# DotControl.net
KiCad netlist of a schematic drawn in EAGLE
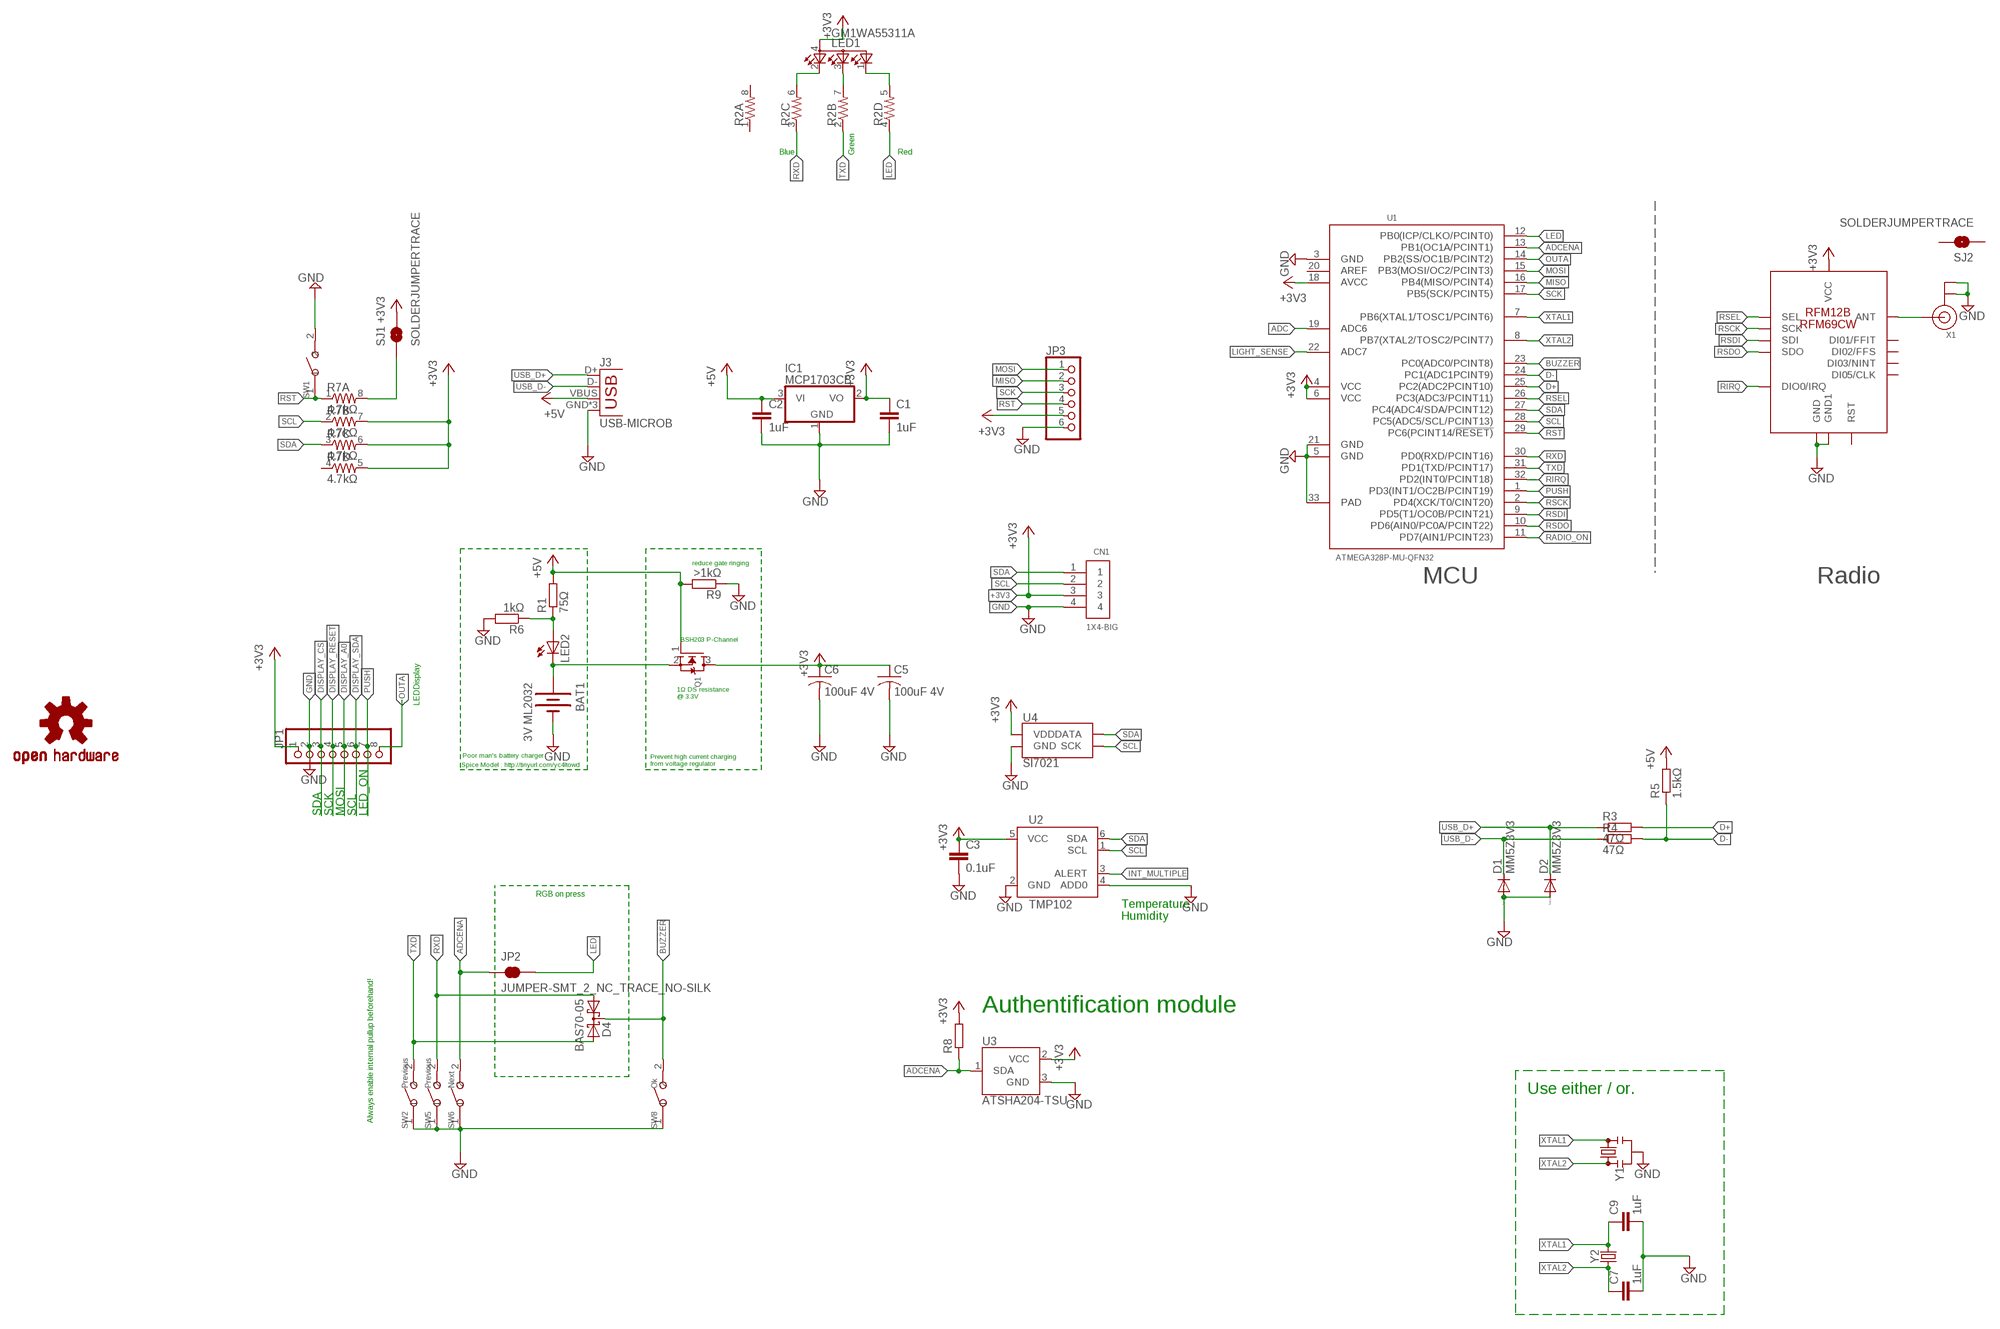
[diagram p0: schematic, sheet 1, part 1 of 2]
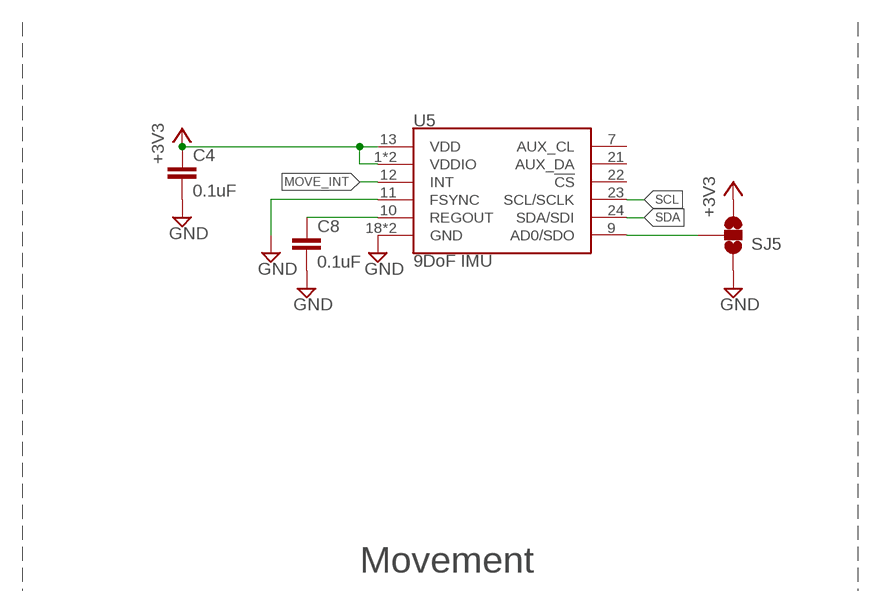
[diagram p1: schematic, sheet 1, part 2 of 2]
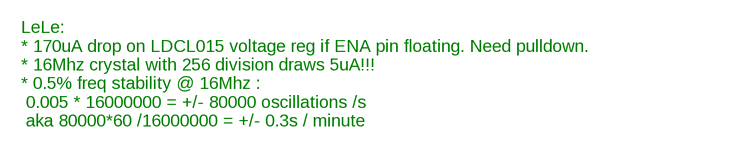
[diagram p2: schematic, sheet 2]

(export (version "E")
  (design (tool "Eeschema 10.0.6"))
  (components
    (comp (ref "BAT1")
      (value "3V ML2032")
      (footprint "eagle-import:BATTCOM_20MM_PTH")
      (libsource (lib "eagle-import") (part "BATTERY20PTH"))
    )
    (comp (ref "C1")
      (value "1uF")
      (footprint "eagle-import:C0603")
      (libsource (lib "eagle-import") (part "C-EUC0603"))
    )
    (comp (ref "C2")
      (value "1uF")
      (footprint "eagle-import:C0603")
      (libsource (lib "eagle-import") (part "C-EUC0603"))
    )
    (comp (ref "C3")
      (value "0.1uF")
      (footprint "eagle-import:C0603")
      (libsource (lib "eagle-import") (part "resistor_C-EUC0603"))
    )
    (comp (ref "C4")
      (value "0.1uF")
      (footprint "eagle-import:C0603")
      (libsource (lib "eagle-import") (part "resistor_C-EUC0603"))
    )
    (comp (ref "C5")
      (value "100uF 4V")
      (footprint "eagle-import:C3216")
      (libsource (lib "eagle-import") (part "C-USC3216"))
    )
    (comp (ref "C6")
      (value "100uF 4V")
      (footprint "eagle-import:C3216")
      (libsource (lib "eagle-import") (part "C-USC3216"))
    )
    (comp (ref "C7")
      (value "1uF")
      (footprint "eagle-import:C0603")
      (libsource (lib "eagle-import") (part "C-EUC0603"))
    )
    (comp (ref "C8")
      (value "0.1uF")
      (footprint "eagle-import:C0603")
      (libsource (lib "eagle-import") (part "resistor_C-EUC0603"))
    )
    (comp (ref "C9")
      (value "1uF")
      (footprint "eagle-import:C0603")
      (libsource (lib "eagle-import") (part "C-EUC0603"))
    )
    (comp (ref "CN1")
      (value "1X4-BIG")
      (footprint "eagle-import:1X04-BIG")
      (libsource (lib "eagle-import") (part "1X4-BIG"))
    )
    (comp (ref "D1")
      (value "MM5Z3V3")
      (footprint "eagle-import:SOD523")
      (libsource (lib "eagle-import") (part "DIODE-SOD523"))
    )
    (comp (ref "D2")
      (value "MM5Z3V3")
      (footprint "eagle-import:SOD523")
      (libsource (lib "eagle-import") (part "DIODE-SOD523"))
    )
    (comp (ref "D4")
      (value "BAS70-05")
      (footprint "eagle-import:SOT23")
      (libsource (lib "eagle-import") (part "BAS70-05"))
    )
    (comp (ref "IC1")
      (value "MCP1703CB")
      (footprint "eagle-import:SOT23")
      (libsource (lib "eagle-import") (part "MCP1703CB"))
    )
    (comp (ref "J3")
      (value "USB-MICROB")
      (footprint "eagle-import:USB-MICROB")
      (libsource (lib "eagle-import") (part "USB-MICROB"))
    )
    (comp (ref "JP1")
      (value "PINHD-1X8CLEANBIG")
      (footprint "eagle-import:1X08-CLEANBIG")
      (libsource (lib "eagle-import") (part "PINHD-1X8CLEANBIG"))
    )
    (comp (ref "JP2")
      (value "JUMPER-SMT_2_NC_TRACE_NO-SILK")
      (footprint "eagle-import:SMT-JUMPER_2_NC_TRACE_NO-SILK")
      (libsource (lib "eagle-import") (part "JUMPER-SMT_2_NC_TRACE_NO-SILK"))
    )
    (comp (ref "JP3")
      (value "PINHD-1X6")
      (footprint "eagle-import:1X06")
      (libsource (lib "eagle-import") (part "PINHD-1X6"))
    )
    (comp (ref "LED1")
      (value "GM1WA55311A")
      (footprint "eagle-import:GM1WA55311A")
      (libsource (lib "eagle-import") (part "GM1WA55311A"))
    )
    (comp (ref "LED2")
      (value "LED0603")
      (footprint "eagle-import:LED-0603")
      (libsource (lib "eagle-import") (part "LED0603"))
    )
    (comp (ref "Q1")
      (value "MOSFET-NREFLOW")
      (footprint "eagle-import:SOT23")
      (libsource (lib "eagle-import") (part "MOSFET-NREFLOW"))
    )
    (comp (ref "R1")
      (value "75Ω")
      (footprint "eagle-import:R0603")
      (libsource (lib "eagle-import") (part "resistor_R-EU_R0603"))
    )
    (comp (ref "R2")
      (value "RESISTOR-ARRAY0603-ARV")
      (footprint "eagle-import:0603-ARV")
      (libsource (lib "eagle-import") (part "RESISTOR-ARRAY0603-ARV"))
    )
    (comp (ref "R3")
      (value "47Ω")
      (footprint "eagle-import:R0603")
      (libsource (lib "eagle-import") (part "R-EU_R0603"))
    )
    (comp (ref "R4")
      (value "47Ω")
      (footprint "eagle-import:R0603")
      (libsource (lib "eagle-import") (part "R-EU_R0603"))
    )
    (comp (ref "R5")
      (value "1.5kΩ")
      (footprint "eagle-import:R0603")
      (libsource (lib "eagle-import") (part "R-EU_R0603"))
    )
    (comp (ref "R6")
      (value "1kΩ")
      (footprint "eagle-import:R0603")
      (libsource (lib "eagle-import") (part "resistor_R-EU_R0603"))
    )
    (comp (ref "R7")
      (value "4.7kΩ")
      (footprint "eagle-import:0603-ARV")
      (libsource (lib "eagle-import") (part "RESISTOR-ARRAY0603-ARV"))
    )
    (comp (ref "R8")
      (value "R-EU_R0603")
      (footprint "eagle-import:R0603")
      (libsource (lib "eagle-import") (part "R-EU_R0603"))
    )
    (comp (ref "R9")
      (value ">1kΩ")
      (footprint "eagle-import:R0603")
      (libsource (lib "eagle-import") (part "resistor_R-EU_R0603"))
    )
    (comp (ref "SJ1")
      (value "SOLDERJUMPERTRACE")
      (footprint "eagle-import:SJ_2S-TRACE")
      (libsource (lib "eagle-import") (part "SOLDERJUMPERTRACE"))
    )
    (comp (ref "SJ2")
      (value "SOLDERJUMPERTRACE")
      (footprint "eagle-import:SJ_2S-TRACE")
      (libsource (lib "eagle-import") (part "SOLDERJUMPERTRACE"))
    )
    (comp (ref "SJ5")
      (value "SOLDERJUMPER_2WAYS")
      (footprint "eagle-import:SJ_3")
      (libsource (lib "eagle-import") (part "SOLDERJUMPER_2WAYS"))
    )
    (comp (ref "SW1")
      (value "SMD-BUTTON(2P-6.0X3.0X2.5MM)-DHT-1163S")
      (footprint "eagle-import:SW2-4.0-6.0X3.0X2.5MM")
      (libsource (lib "eagle-import") (part "SMD-BUTTON(2P-6.0X3.0X2.5MM)-DHT-1163S"))
    )
    (comp (ref "SW2")
      (value "Previous")
      (footprint "eagle-import:SW2-4.0-6.0X3.0X2.5MM")
      (libsource (lib "eagle-import") (part "SMD-BUTTON(2P-6.0X3.0X2.5MM)-DHT-1163S"))
    )
    (comp (ref "SW5")
      (value "Previous")
      (footprint "eagle-import:SW2-4.0-6.0X3.0X2.5MM")
      (libsource (lib "eagle-import") (part "SMD-BUTTON(2P-6.0X3.0X2.5MM)-DHT-1163S"))
    )
    (comp (ref "SW6")
      (value "Next")
      (footprint "eagle-import:SW2-4.0-6.0X3.0X2.5MM")
      (libsource (lib "eagle-import") (part "SMD-BUTTON(2P-6.0X3.0X2.5MM)-DHT-1163S"))
    )
    (comp (ref "SW8")
      (value "Ok")
      (footprint "eagle-import:SW2-4.0-6.0X3.0X2.5MM")
      (libsource (lib "eagle-import") (part "SMD-BUTTON(2P-6.0X3.0X2.5MM)-DHT-1163S"))
    )
    (comp (ref "U$1")
      (value "RFM12B/69CW")
      (footprint "eagle-import:RFM12B_69CW")
      (libsource (lib "eagle-import") (part "RFM12B/69CW"))
    )
    (comp (ref "U$2")
      (value "OSHW-LOGOL")
      (footprint "eagle-import:OSHW-LOGO-L")
      (libsource (lib "eagle-import") (part "OSHW-LOGOL"))
    )
    (comp (ref "U1")
      (value "ATMEGA328P-MU-QFN32")
      (footprint "eagle-import:QFN32G-0.5-5X5MM")
      (fields (field (name "MPN") "ATMEGA328P-MU"))
      (libsource (lib "eagle-import") (part "MCU-ATMEGA328P-MU(QFN32)"))
    )
    (comp (ref "U2")
      (value "TMP102")
      (footprint "eagle-import:SOT563")
      (libsource (lib "eagle-import") (part "TMP102"))
    )
    (comp (ref "U3")
      (value "ATSHA204-TSU")
      (footprint "eagle-import:SOT23-3")
      (libsource (lib "eagle-import") (part "ATSHA204-TSU"))
    )
    (comp (ref "U4")
      (value "SI7021")
      (footprint "eagle-import:DFN-6-3X3-SI7021")
      (libsource (lib "eagle-import") (part "SI7021"))
    )
    (comp (ref "U5")
      (value "9DoF IMU")
      (footprint "eagle-import:QFN24-3X3")
      (libsource (lib "eagle-import") (part "MPU-9250"))
    )
    (comp (ref "X1")
      (value "ANTENNA_U.FL")
      (footprint "eagle-import:U.FL")
      (libsource (lib "eagle-import") (part "ANTENNA_U.FL"))
    )
    (comp (ref "Y1")
      (value "RESONATORSMD-3.2X1.3")
      (footprint "eagle-import:RESONATOR-SMD-3.2X1.3")
      (libsource (lib "eagle-import") (part "RESONATORSMD-3.2X1.3"))
    )
    (comp (ref "Y2")
      (value "CRYSTALSMD-3.2X1.5")
      (footprint "eagle-import:CRYSTAL-SMD-3.2X1.5MM")
      (libsource (lib "eagle-import") (part "CRYSTALSMD-3.2X1.5"))
    )
  )
  (nets
    (net (code "1") (name "+3V3") (class "Default")
      (node (ref "C1") (pin "1") (pinfunction "1_1") (pintype "passive"))
      (node (ref "C3") (pin "1") (pinfunction "1_1") (pintype "passive"))
      (node (ref "C4") (pin "1") (pinfunction "1_1") (pintype "passive"))
      (node (ref "C5") (pin "1") (pinfunction "1_1") (pintype "passive"))
      (node (ref "C6") (pin "1") (pinfunction "1_1") (pintype "passive"))
      (node (ref "CN1") (pin "3") (pinfunction "3_3") (pintype "bidirectional"))
      (node (ref "IC1") (pin "2") (pinfunction "VO_2") (pintype "passive"))
      (node (ref "JP1") (pin "1") (pinfunction "1_1") (pintype "passive"))
      (node (ref "JP3") (pin "5") (pinfunction "5_5") (pintype "passive"))
      (node (ref "LED1") (pin "4") (pinfunction "A_4") (pintype "passive"))
      (node (ref "Q1") (pin "3") (pinfunction "D_3") (pintype "bidirectional"))
      (node (ref "R7") (pin "5") (pinfunction "2_5") (pintype "passive"))
      (node (ref "R7") (pin "6") (pinfunction "2_6") (pintype "passive"))
      (node (ref "R7") (pin "7") (pinfunction "2_7") (pintype "passive"))
      (node (ref "R8") (pin "2") (pinfunction "2_2") (pintype "passive"))
      (node (ref "SJ1") (pin "2") (pinfunction "2_2") (pintype "passive"))
      (node (ref "SJ5") (pin "3") (pinfunction "3_3") (pintype "passive"))
      (node (ref "U$1") (pin "VDD") (pinfunction "VCC_VDD") (pintype "power_in"))
      (node (ref "U1") (pin "18") (pinfunction "AVCC_18") (pintype "bidirectional"))
      (node (ref "U1") (pin "4") (pinfunction "VCC_4") (pintype "bidirectional"))
      (node (ref "U1") (pin "6") (pinfunction "VCC_6") (pintype "bidirectional"))
      (node (ref "U2") (pin "5") (pinfunction "VCC_5") (pintype "bidirectional"))
      (node (ref "U3") (pin "2") (pinfunction "VCC_2") (pintype "bidirectional"))
      (node (ref "U4") (pin "VDD") (pinfunction "VDD_VDD") (pintype "power_in"))
      (node (ref "U5") (pin "1") (pinfunction "VDDIO_1") (pintype "bidirectional"))
      (node (ref "U5") (pin "13") (pinfunction "VDD_13") (pintype "bidirectional"))
      (node (ref "U5") (pin "8") (pinfunction "VDDIO_8") (pintype "bidirectional"))
    )
    (net (code "2") (name "+5V") (class "Default")
      (node (ref "C2") (pin "1") (pinfunction "1_1") (pintype "passive"))
      (node (ref "IC1") (pin "3") (pinfunction "VI_3") (pintype "input"))
      (node (ref "J3") (pin "VBUS") (pinfunction "VBUS_VBUS") (pintype "bidirectional"))
      (node (ref "Q1") (pin "1") (pinfunction "G_1") (pintype "bidirectional"))
      (node (ref "R1") (pin "2") (pinfunction "2_2") (pintype "passive"))
      (node (ref "R5") (pin "2") (pinfunction "2_2") (pintype "passive"))
      (node (ref "R9") (pin "2") (pinfunction "2_2") (pintype "passive"))
    )
    (net (code "3") (name "ADC") (class "Default")
      (node (ref "U1") (pin "19") (pinfunction "ADC6_19") (pintype "bidirectional"))
    )
    (net (code "4") (name "ADCENA") (class "Default")
      (node (ref "JP2") (pin "1") (pinfunction "1_1") (pintype "passive"))
      (node (ref "R8") (pin "1") (pinfunction "1_1") (pintype "passive"))
      (node (ref "SW6") (pin "2") (pinfunction "2_2") (pintype "bidirectional"))
      (node (ref "U1") (pin "13") (pinfunction "PB1(OC1A/PCINT1)_13") (pintype "bidirectional"))
      (node (ref "U3") (pin "1") (pinfunction "SDA_1") (pintype "bidirectional"))
    )
    (net (code "5") (name "BUZZER") (class "Default")
      (node (ref "D4") (pin "3") (pinfunction "C_3") (pintype "passive"))
      (node (ref "SW8") (pin "2") (pinfunction "2_2") (pintype "bidirectional"))
      (node (ref "U1") (pin "23") (pinfunction "PC0(ADC0/PCINT8)_23") (pintype "bidirectional"))
    )
    (net (code "6") (name "D+") (class "Default")
      (node (ref "R3") (pin "2") (pinfunction "2_2") (pintype "passive"))
      (node (ref "U1") (pin "25") (pinfunction "PC2(ADC2PCINT10)_25") (pintype "bidirectional"))
    )
    (net (code "7") (name "D-") (class "Default")
      (node (ref "R4") (pin "2") (pinfunction "2_2") (pintype "passive"))
      (node (ref "R5") (pin "1") (pinfunction "1_1") (pintype "passive"))
      (node (ref "U1") (pin "24") (pinfunction "PC1(ADC1PCINT9)_24") (pintype "bidirectional"))
    )
    (net (code "8") (name "DISPLAY_A0") (class "Default")
      (node (ref "JP1") (pin "5") (pinfunction "5_5") (pintype "passive"))
    )
    (net (code "9") (name "DISPLAY_CS") (class "Default")
      (node (ref "JP1") (pin "3") (pinfunction "3_3") (pintype "passive"))
    )
    (net (code "10") (name "DISPLAY_RESET") (class "Default")
      (node (ref "JP1") (pin "4") (pinfunction "4_4") (pintype "passive"))
    )
    (net (code "11") (name "DISPLAY_SDA") (class "Default")
      (node (ref "JP1") (pin "6") (pinfunction "6_6") (pintype "passive"))
    )
    (net (code "12") (name "GND") (class "Default")
      (node (ref "BAT1") (pin "2") (pinfunction "-_2") (pintype "power_in"))
      (node (ref "C1") (pin "2") (pinfunction "2_2") (pintype "passive"))
      (node (ref "C2") (pin "2") (pinfunction "2_2") (pintype "passive"))
      (node (ref "C3") (pin "2") (pinfunction "2_2") (pintype "passive"))
      (node (ref "C4") (pin "2") (pinfunction "2_2") (pintype "passive"))
      (node (ref "C5") (pin "2") (pinfunction "2_2") (pintype "passive"))
      (node (ref "C6") (pin "2") (pinfunction "2_2") (pintype "passive"))
      (node (ref "C7") (pin "2") (pinfunction "2_2") (pintype "passive"))
      (node (ref "C8") (pin "2") (pinfunction "2_2") (pintype "passive"))
      (node (ref "C9") (pin "2") (pinfunction "2_2") (pintype "passive"))
      (node (ref "CN1") (pin "4") (pinfunction "4_4") (pintype "bidirectional"))
      (node (ref "D1") (pin "A") (pinfunction "A_A") (pintype "passive"))
      (node (ref "D2") (pin "A") (pinfunction "A_A") (pintype "passive"))
      (node (ref "IC1") (pin "1") (pinfunction "GND_1") (pintype "passive"))
      (node (ref "J3") (pin "GND") (pinfunction "GND_GND") (pintype "bidirectional"))
      (node (ref "J3") (pin "MT1") (pinfunction "GND_MT1") (pintype "bidirectional"))
      (node (ref "J3") (pin "MT2") (pinfunction "GND_MT2") (pintype "bidirectional"))
      (node (ref "JP1") (pin "2") (pinfunction "2_2") (pintype "passive"))
      (node (ref "JP3") (pin "6") (pinfunction "6_6") (pintype "passive"))
      (node (ref "R6") (pin "2") (pinfunction "2_2") (pintype "passive"))
      (node (ref "R9") (pin "1") (pinfunction "1_1") (pintype "passive"))
      (node (ref "SJ5") (pin "1") (pinfunction "1_1") (pintype "passive"))
      (node (ref "SW1") (pin "2") (pinfunction "2_2") (pintype "bidirectional"))
      (node (ref "SW2") (pin "1") (pinfunction "1_1") (pintype "bidirectional"))
      (node (ref "SW5") (pin "1") (pinfunction "1_1") (pintype "bidirectional"))
      (node (ref "SW6") (pin "1") (pinfunction "1_1") (pintype "bidirectional"))
      (node (ref "SW8") (pin "1") (pinfunction "1_1") (pintype "bidirectional"))
      (node (ref "U$1") (pin "GND") (pinfunction "GND_GND") (pintype "power_in"))
      (node (ref "U$1") (pin "GND1") (pinfunction "GND1_GND1") (pintype "power_in"))
      (node (ref "U1") (pin "21") (pinfunction "GND_21") (pintype "bidirectional"))
      (node (ref "U1") (pin "3") (pinfunction "GND_3") (pintype "bidirectional"))
      (node (ref "U1") (pin "33") (pinfunction "PAD_33") (pintype "bidirectional"))
      (node (ref "U1") (pin "5") (pinfunction "GND_5") (pintype "bidirectional"))
      (node (ref "U2") (pin "2") (pinfunction "GND_2") (pintype "bidirectional"))
      (node (ref "U2") (pin "4") (pinfunction "ADD0_4") (pintype "bidirectional"))
      (node (ref "U3") (pin "3") (pinfunction "GND_3") (pintype "bidirectional"))
      (node (ref "U4") (pin "GND") (pinfunction "GND_GND") (pintype "power_in"))
      (node (ref "U5") (pin "11") (pinfunction "FSYNC_11") (pintype "bidirectional"))
      (node (ref "U5") (pin "18") (pinfunction "GND_18") (pintype "bidirectional"))
      (node (ref "U5") (pin "20") (pinfunction "GND_20") (pintype "bidirectional"))
      (node (ref "X1") (pin "1") (pinfunction "GND_1") (pintype "passive"))
      (node (ref "X1") (pin "2") (pinfunction "GND_2") (pintype "passive"))
      (node (ref "Y1") (pin "2") (pinfunction "2_2") (pintype "passive"))
    )
    (net (code "13") (name "INT_MULTIPLE") (class "Default")
      (node (ref "U2") (pin "3") (pinfunction "ALERT_3") (pintype "bidirectional"))
    )
    (net (code "14") (name "LED") (class "Default")
      (node (ref "JP2") (pin "2") (pinfunction "2_2") (pintype "passive"))
      (node (ref "R2") (pin "4") (pinfunction "1_4") (pintype "passive"))
      (node (ref "U1") (pin "12") (pinfunction "PB0(ICP/CLKO/PCINT0)_12") (pintype "bidirectional"))
    )
    (net (code "15") (name "LIGHT_SENSE") (class "Default")
      (node (ref "U1") (pin "22") (pinfunction "ADC7_22") (pintype "bidirectional"))
    )
    (net (code "16") (name "MISO") (class "Default")
      (node (ref "JP3") (pin "2") (pinfunction "2_2") (pintype "passive"))
      (node (ref "U1") (pin "16") (pinfunction "PB4(MISO/PCINT4)_16") (pintype "bidirectional"))
    )
    (net (code "17") (name "MOSI") (class "Default")
      (node (ref "JP3") (pin "1") (pinfunction "1_1") (pintype "passive"))
      (node (ref "U1") (pin "15") (pinfunction "PB3(MOSI/OC2/PCINT3)_15") (pintype "bidirectional"))
    )
    (net (code "18") (name "MOVE_INT") (class "Default")
      (node (ref "U5") (pin "12") (pinfunction "INT_12") (pintype "bidirectional"))
    )
    (net (code "19") (name "Net-(BAT1-+)") (class "Default")
      (node (ref "BAT1") (pin "1") (pinfunction "+_1") (pintype "power_in"))
      (node (ref "LED2") (pin "C") (pinfunction "C_C") (pintype "passive"))
      (node (ref "Q1") (pin "2") (pinfunction "S_2") (pintype "bidirectional"))
    )
    (net (code "20") (name "Net-(LED1-CBLUE)") (class "Default")
      (node (ref "LED1") (pin "3") (pinfunction "CBLUE_3") (pintype "passive"))
      (node (ref "R2") (pin "7") (pinfunction "2_7") (pintype "passive"))
    )
    (net (code "21") (name "Net-(LED1-CGREEN)") (class "Default")
      (node (ref "LED1") (pin "1") (pinfunction "CGREEN_1") (pintype "passive"))
      (node (ref "R2") (pin "5") (pinfunction "2_5") (pintype "passive"))
    )
    (net (code "22") (name "Net-(LED1-CRED)") (class "Default")
      (node (ref "LED1") (pin "2") (pinfunction "CRED_2") (pintype "passive"))
      (node (ref "R2") (pin "6") (pinfunction "2_6") (pintype "passive"))
    )
    (net (code "23") (name "Net-(LED2-PadA)") (class "Default")
      (node (ref "LED2") (pin "A") (pinfunction "A_A") (pintype "passive"))
      (node (ref "R1") (pin "1") (pinfunction "1_1") (pintype "passive"))
      (node (ref "R6") (pin "1") (pinfunction "1_1") (pintype "passive"))
    )
    (net (code "24") (name "Net-(R7A-2)") (class "Default")
      (node (ref "R7") (pin "8") (pinfunction "2_8") (pintype "passive"))
      (node (ref "SJ1") (pin "1") (pinfunction "1_1") (pintype "passive"))
    )
    (net (code "25") (name "Net-(U5-AD0{slash}SDO)") (class "Default")
      (node (ref "SJ5") (pin "2") (pinfunction "2_2") (pintype "passive"))
      (node (ref "U5") (pin "9") (pinfunction "AD0/SDO_9") (pintype "bidirectional"))
    )
    (net (code "26") (name "Net-(U5-REGOUT)") (class "Default")
      (node (ref "C8") (pin "1") (pinfunction "1_1") (pintype "passive"))
      (node (ref "U5") (pin "10") (pinfunction "REGOUT_10") (pintype "bidirectional"))
    )
    (net (code "27") (name "Net-(X1-SIGNAL)") (class "Default")
      (node (ref "U$1") (pin "ANT") (pinfunction "ANT_ANT") (pintype "passive"))
      (node (ref "X1") (pin "3") (pinfunction "SIGNAL_3") (pintype "passive"))
    )
    (net (code "28") (name "OUTA") (class "Default")
      (node (ref "JP1") (pin "8") (pinfunction "8_8") (pintype "passive"))
      (node (ref "U1") (pin "14") (pinfunction "PB2(SS/OC1B/PCINT2)_14") (pintype "bidirectional"))
    )
    (net (code "29") (name "PUSH") (class "Default")
      (node (ref "JP1") (pin "7") (pinfunction "7_7") (pintype "passive"))
      (node (ref "U1") (pin "1") (pinfunction "PD3(INT1/OC2B/PCINT19)_1") (pintype "bidirectional"))
    )
    (net (code "30") (name "RADIO_ON") (class "Default")
      (node (ref "U1") (pin "11") (pinfunction "PD7(AIN1/PCINT23)_11") (pintype "bidirectional"))
    )
    (net (code "31") (name "RIRQ") (class "Default")
      (node (ref "U$1") (pin "IRQ") (pinfunction "DIO0/IRQ_IRQ") (pintype "open_collector"))
      (node (ref "U1") (pin "32") (pinfunction "PD2(INT0/PCINT18)_32") (pintype "bidirectional"))
    )
    (net (code "32") (name "RSCK") (class "Default")
      (node (ref "U$1") (pin "SCK") (pinfunction "SCK_SCK") (pintype "input"))
      (node (ref "U1") (pin "2") (pinfunction "PD4(XCK/T0/CINT20)_2") (pintype "bidirectional"))
    )
    (net (code "33") (name "RSDI") (class "Default")
      (node (ref "U$1") (pin "SDI") (pinfunction "SDI_SDI") (pintype "input"))
      (node (ref "U1") (pin "9") (pinfunction "PD5(T1/OC0B/PCINT21)_9") (pintype "bidirectional"))
    )
    (net (code "34") (name "RSDO") (class "Default")
      (node (ref "U$1") (pin "SDO") (pinfunction "SDO_SDO") (pintype "output"))
      (node (ref "U1") (pin "10") (pinfunction "PD6(AIN0/PC0A/PCINT22)_10") (pintype "bidirectional"))
    )
    (net (code "35") (name "RSEL") (class "Default")
      (node (ref "U$1") (pin "SEL") (pinfunction "SEL_SEL") (pintype "input"))
      (node (ref "U1") (pin "26") (pinfunction "PC3(ADC3/PCINT11)_26") (pintype "bidirectional"))
    )
    (net (code "36") (name "RST") (class "Default")
      (node (ref "JP3") (pin "4") (pinfunction "4_4") (pintype "passive"))
      (node (ref "R7") (pin "1") (pinfunction "1_1") (pintype "passive"))
      (node (ref "SW1") (pin "1") (pinfunction "1_1") (pintype "bidirectional"))
      (node (ref "U1") (pin "29") (pinfunction "PC6(PCINT14/~{RESET})_29") (pintype "bidirectional"))
    )
    (net (code "37") (name "RXD") (class "Default")
      (node (ref "D4") (pin "1") (pinfunction "A1_1") (pintype "passive"))
      (node (ref "R2") (pin "3") (pinfunction "1_3") (pintype "passive"))
      (node (ref "SW5") (pin "2") (pinfunction "2_2") (pintype "bidirectional"))
      (node (ref "U1") (pin "30") (pinfunction "PD0(RXD/PCINT16)_30") (pintype "bidirectional"))
    )
    (net (code "38") (name "SCK") (class "Default")
      (node (ref "JP3") (pin "3") (pinfunction "3_3") (pintype "passive"))
      (node (ref "U1") (pin "17") (pinfunction "PB5(SCK/PCINT5)_17") (pintype "bidirectional"))
    )
    (net (code "39") (name "SCL") (class "Default")
      (node (ref "CN1") (pin "2") (pinfunction "2_2") (pintype "bidirectional"))
      (node (ref "R7") (pin "2") (pinfunction "1_2") (pintype "passive"))
      (node (ref "U1") (pin "28") (pinfunction "PC5(ADC5/SCL/PCINT13)_28") (pintype "bidirectional"))
      (node (ref "U2") (pin "1") (pinfunction "SCL_1") (pintype "bidirectional"))
      (node (ref "U4") (pin "SCK") (pinfunction "SCK_SCK") (pintype "input"))
      (node (ref "U5") (pin "23") (pinfunction "SCL/SCLK_23") (pintype "bidirectional"))
    )
    (net (code "40") (name "SDA") (class "Default")
      (node (ref "CN1") (pin "1") (pinfunction "1_1") (pintype "bidirectional"))
      (node (ref "R7") (pin "3") (pinfunction "1_3") (pintype "passive"))
      (node (ref "U1") (pin "27") (pinfunction "PC4(ADC4/SDA/PCINT12)_27") (pintype "bidirectional"))
      (node (ref "U2") (pin "6") (pinfunction "SDA_6") (pintype "bidirectional"))
      (node (ref "U4") (pin "DATA") (pinfunction "DATA_DATA") (pintype "bidirectional"))
      (node (ref "U5") (pin "24") (pinfunction "SDA/SDI_24") (pintype "bidirectional"))
    )
    (net (code "41") (name "TXD") (class "Default")
      (node (ref "D4") (pin "2") (pinfunction "A2_2") (pintype "passive"))
      (node (ref "R2") (pin "2") (pinfunction "1_2") (pintype "passive"))
      (node (ref "SW2") (pin "2") (pinfunction "2_2") (pintype "bidirectional"))
      (node (ref "U1") (pin "31") (pinfunction "PD1(TXD/PCINT17)_31") (pintype "bidirectional"))
    )
    (net (code "42") (name "USB_D+") (class "Default")
      (node (ref "D2") (pin "C") (pinfunction "C_C") (pintype "passive"))
      (node (ref "J3") (pin "D+") (pinfunction "D+_D+") (pintype "bidirectional"))
      (node (ref "R3") (pin "1") (pinfunction "1_1") (pintype "passive"))
    )
    (net (code "43") (name "USB_D-") (class "Default")
      (node (ref "D1") (pin "C") (pinfunction "C_C") (pintype "passive"))
      (node (ref "J3") (pin "D-") (pinfunction "D-_D-") (pintype "bidirectional"))
      (node (ref "R4") (pin "1") (pinfunction "1_1") (pintype "passive"))
    )
    (net (code "44") (name "XTAL1") (class "Default")
      (node (ref "C9") (pin "1") (pinfunction "1_1") (pintype "passive"))
      (node (ref "U1") (pin "7") (pinfunction "PB6(XTAL1/TOSC1/PCINT6)_7") (pintype "bidirectional"))
      (node (ref "Y1") (pin "3") (pinfunction "3_3") (pintype "passive"))
      (node (ref "Y2") (pin "P$2") (pinfunction "2_P$2") (pintype "passive"))
    )
    (net (code "45") (name "XTAL2") (class "Default")
      (node (ref "C7") (pin "1") (pinfunction "1_1") (pintype "passive"))
      (node (ref "U1") (pin "8") (pinfunction "PB7(XTAL2/TOSC2/PCINT7)_8") (pintype "bidirectional"))
      (node (ref "Y1") (pin "1") (pinfunction "1_1") (pintype "passive"))
      (node (ref "Y2") (pin "P$1") (pinfunction "1_P$1") (pintype "passive"))
    )
    (net (code "46") (name "unconnected-(R2-Pad1)") (class "Default")
      (node (ref "R2") (pin "1") (pinfunction "1_1") (pintype "passive"))
    )
    (net (code "47") (name "unconnected-(R2A-2-Pad8)") (class "Default")
      (node (ref "R2") (pin "8") (pinfunction "2_8") (pintype "passive"))
    )
    (net (code "48") (name "unconnected-(R7D-1-Pad4)") (class "Default")
      (node (ref "R7") (pin "4") (pinfunction "1_4") (pintype "passive"))
    )
    (net (code "49") (name "unconnected-(SJ2-Pad1)") (class "Default")
      (node (ref "SJ2") (pin "1") (pinfunction "1_1") (pintype "passive"))
    )
    (net (code "50") (name "unconnected-(SJ2-Pad2)") (class "Default")
      (node (ref "SJ2") (pin "2") (pinfunction "2_2") (pintype "passive"))
    )
    (net (code "51") (name "unconnected-(U$1-DI01{slash}FFIT-PadFFIT)") (class "Default")
      (node (ref "U$1") (pin "FFIT") (pinfunction "DI01/FFIT_FFIT") (pintype "passive"))
    )
    (net (code "52") (name "unconnected-(U$1-DI02{slash}FFS-PadFFS)") (class "Default")
      (node (ref "U$1") (pin "FFS") (pinfunction "DI02/FFS_FFS") (pintype "bidirectional"))
    )
    (net (code "53") (name "unconnected-(U$1-DI03{slash}NINT-PadNINT)") (class "Default")
      (node (ref "U$1") (pin "NINT") (pinfunction "DI03/NINT_NINT") (pintype "passive"))
    )
    (net (code "54") (name "unconnected-(U$1-DI05{slash}CLK-PadCLK)") (class "Default")
      (node (ref "U$1") (pin "CLK") (pinfunction "DI05/CLK_CLK") (pintype "passive"))
    )
    (net (code "55") (name "unconnected-(U$1-PadRST)") (class "Default")
      (node (ref "U$1") (pin "RST") (pinfunction "RST_RST") (pintype "open_collector"))
    )
    (net (code "56") (name "unconnected-(U1-AREF-Pad20)") (class "Default")
      (node (ref "U1") (pin "20") (pinfunction "AREF_20") (pintype "bidirectional"))
    )
    (net (code "57") (name "unconnected-(U5-AUX_CL-Pad7)") (class "Default")
      (node (ref "U5") (pin "7") (pinfunction "AUX_CL_7") (pintype "bidirectional"))
    )
    (net (code "58") (name "unconnected-(U5-AUX_DA-Pad21)") (class "Default")
      (node (ref "U5") (pin "21") (pinfunction "AUX_DA_21") (pintype "bidirectional"))
    )
    (net (code "59") (name "unconnected-(U5-~{CS}-Pad22)") (class "Default")
      (node (ref "U5") (pin "22") (pinfunction "~{CS}_22") (pintype "bidirectional"))
    )
  )
)
